# F103C8T6.net
KiCad netlist of a schematic drawn in Altium Designer
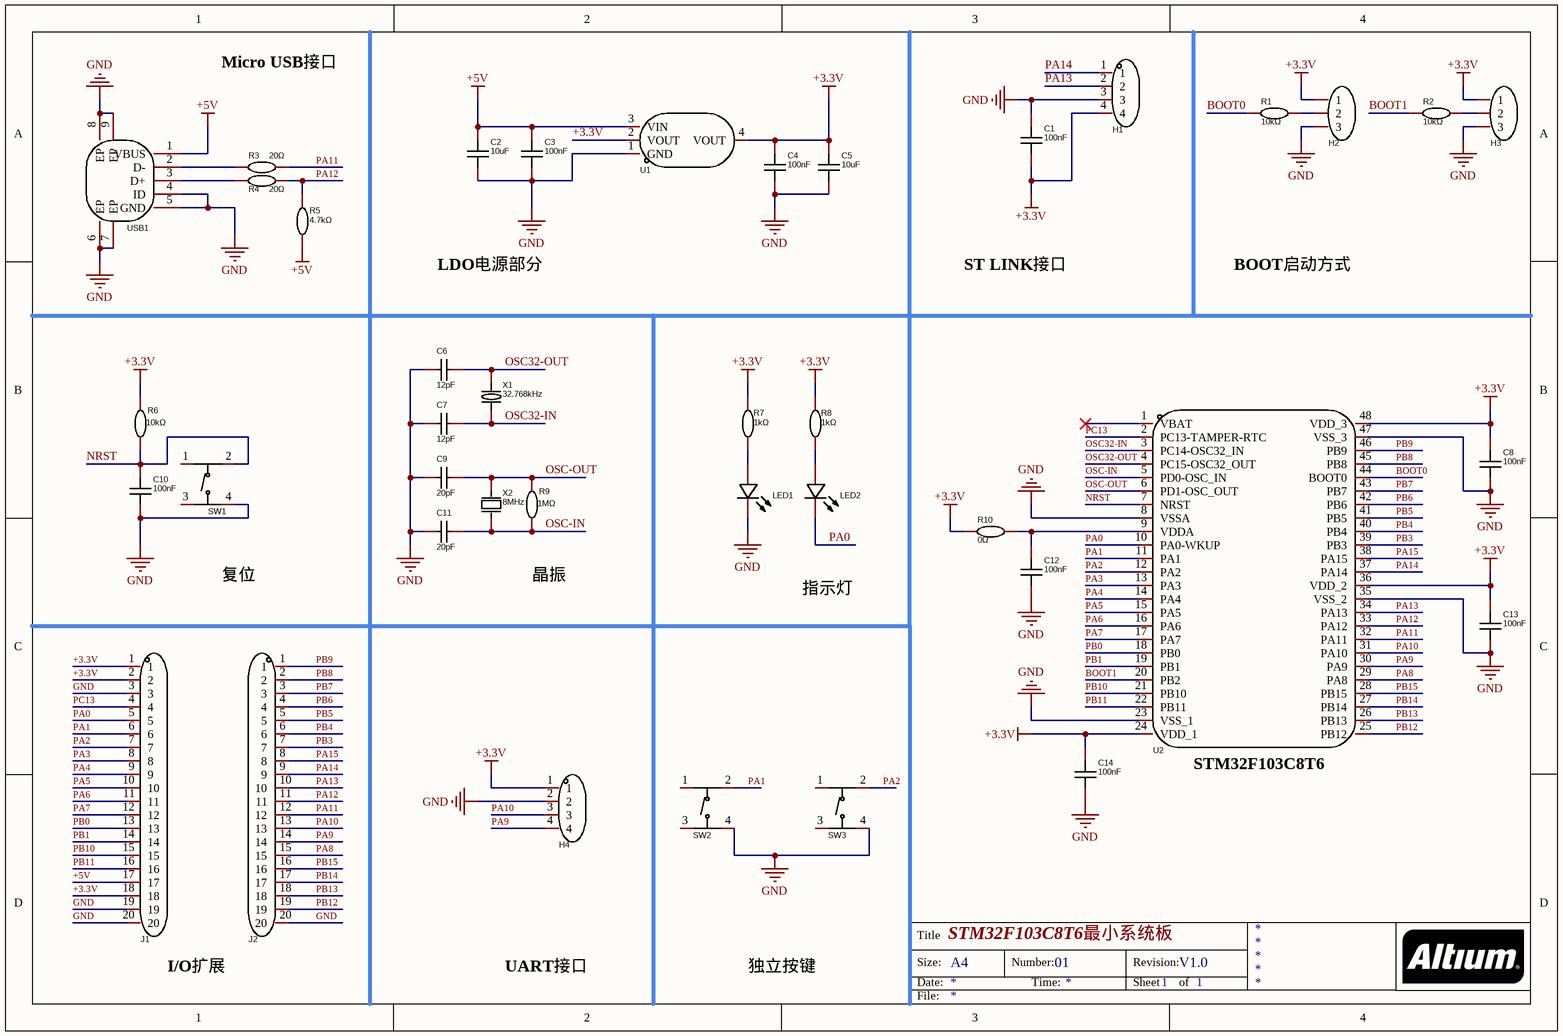
[diagram p0: F103C8T6.SchDoc]

(export (version "E")
  (design (tool "Eeschema 10.0.6"))
  (components
    (comp (ref "C1")
      (value "100nF")
      (footprint "C0603")
      (fields
        (field (name "MANUFACTURER") "YAGEO(国巨)")
        (field (name "MANUFACTURER PART") "CC0603KRX7R9BB104")
        (field (name "TOLERANCE") "±10%")
      )
      (libsource (lib "F103C8T6") (part "CAP_100nf"))
    )
    (comp (ref "C2")
      (value "10uF")
      (footprint "C0603")
      (fields
        (field (name "MANUFACTURER") "SAMSUNG(三星)")
        (field (name "MANUFACTURER PART") "CL10A106MA8NRNC")
        (field (name "TOLERANCE") "±20%")
      )
      (libsource (lib "F103C8T6") (part "CAP_10uf"))
    )
    (comp (ref "C3")
      (value "100nF")
      (footprint "C0603")
      (fields
        (field (name "MANUFACTURER") "YAGEO(国巨)")
        (field (name "MANUFACTURER PART") "CC0603KRX7R9BB104")
        (field (name "TOLERANCE") "±10%")
      )
      (libsource (lib "F103C8T6") (part "CAP_100nf"))
    )
    (comp (ref "C4")
      (value "100nF")
      (footprint "C0603")
      (fields
        (field (name "MANUFACTURER") "YAGEO(国巨)")
        (field (name "MANUFACTURER PART") "CC0603KRX7R9BB104")
        (field (name "TOLERANCE") "±10%")
      )
      (libsource (lib "F103C8T6") (part "CAP_100nf"))
    )
    (comp (ref "C5")
      (value "10uF")
      (footprint "C0603")
      (fields
        (field (name "MANUFACTURER") "SAMSUNG(三星)")
        (field (name "MANUFACTURER PART") "CL10A106MA8NRNC")
        (field (name "TOLERANCE") "±20%")
      )
      (libsource (lib "F103C8T6") (part "CAP_10uf"))
    )
    (comp (ref "C6")
      (value "12pF")
      (footprint "C0603")
      (fields
        (field (name "MANUFACTURER") "SAMSUNG(三星)")
        (field (name "MANUFACTURER PART") "CL10C120JB8NNNC")
        (field (name "TOLERANCE") "±5%")
      )
      (libsource (lib "F103C8T6") (part "CAP_12pf_0603"))
    )
    (comp (ref "C7")
      (value "12pF")
      (footprint "C0603")
      (fields
        (field (name "MANUFACTURER") "SAMSUNG(三星)")
        (field (name "MANUFACTURER PART") "CL10C120JB8NNNC")
        (field (name "TOLERANCE") "±5%")
      )
      (libsource (lib "F103C8T6") (part "CAP_12pf_0603"))
    )
    (comp (ref "C8")
      (value "100nF")
      (footprint "C0603")
      (fields
        (field (name "MANUFACTURER") "YAGEO(国巨)")
        (field (name "MANUFACTURER PART") "CC0603KRX7R9BB104")
        (field (name "TOLERANCE") "±10%")
      )
      (libsource (lib "F103C8T6") (part "CAP_100nf"))
    )
    (comp (ref "C9")
      (value "20pF")
      (footprint "C0603")
      (fields
        (field (name "MANUFACTURER") "SAMSUNG(三星)")
        (field (name "MANUFACTURER PART") "CL10C200JB8NNNC")
        (field (name "TOLERANCE") "±5%")
      )
      (libsource (lib "F103C8T6") (part "CAP_20pf_0603"))
    )
    (comp (ref "C10")
      (value "100nF")
      (footprint "C0603")
      (fields
        (field (name "MANUFACTURER") "YAGEO(国巨)")
        (field (name "MANUFACTURER PART") "CC0603KRX7R9BB104")
        (field (name "TOLERANCE") "±10%")
      )
      (libsource (lib "F103C8T6") (part "CAP_100nf"))
    )
    (comp (ref "C11")
      (value "20pF")
      (footprint "C0603")
      (fields
        (field (name "MANUFACTURER") "SAMSUNG(三星)")
        (field (name "MANUFACTURER PART") "CL10C200JB8NNNC")
        (field (name "TOLERANCE") "±5%")
      )
      (libsource (lib "F103C8T6") (part "CAP_20pf_0603"))
    )
    (comp (ref "C12")
      (value "100nF")
      (footprint "C0603")
      (fields
        (field (name "MANUFACTURER") "YAGEO(国巨)")
        (field (name "MANUFACTURER PART") "CC0603KRX7R9BB104")
        (field (name "TOLERANCE") "±10%")
      )
      (libsource (lib "F103C8T6") (part "CAP_100nf"))
    )
    (comp (ref "C13")
      (value "100nF")
      (footprint "C0603")
      (fields
        (field (name "MANUFACTURER") "YAGEO(国巨)")
        (field (name "MANUFACTURER PART") "CC0603KRX7R9BB104")
        (field (name "TOLERANCE") "±10%")
      )
      (libsource (lib "F103C8T6") (part "CAP_100nf"))
    )
    (comp (ref "C14")
      (value "100nF")
      (footprint "C0603")
      (fields
        (field (name "MANUFACTURER") "YAGEO(国巨)")
        (field (name "MANUFACTURER PART") "CC0603KRX7R9BB104")
        (field (name "TOLERANCE") "±10%")
      )
      (libsource (lib "F103C8T6") (part "CAP_100nf"))
    )
    (comp (ref "H1")
      (value "2.54-1*4P反弯排针")
      (footprint "HDR-TH_4P-P2.54-H-M-W10.4")
      (fields (field (name "MANUFACTURER") "BOOMELE(博穆精密)"))
      (libsource (lib "F103C8T6") (part "2.54-1*4P反弯排针"))
    )
    (comp (ref "H2")
      (value "2.54-1*3P针")
      (footprint "HDR-TH_3P-P2.54-V-M-1")
      (fields (field (name "MANUFACTURER") "BOOMELE(博穆精密)"))
      (libsource (lib "F103C8T6") (part "2.54-1*3P针"))
    )
    (comp (ref "H3")
      (value "2.54-1*3P针")
      (footprint "HDR-TH_3P-P2.54-V-M-1")
      (fields (field (name "MANUFACTURER") "BOOMELE(博穆精密)"))
      (libsource (lib "F103C8T6") (part "2.54-1*3P针"))
    )
    (comp (ref "H4")
      (value "PZ254V-11-04P")
      (footprint "HDR-TH_4P-P2.54-V-M")
      (fields (field (name "MANUFACTURER") "XFCN(兴飞)"))
      (libsource (lib "F103C8T6") (part "2.54-1*4P直针"))
    )
    (comp (ref "J1")
      (value "2.54-1*20P直针")
      (footprint "HDR-TH_20P-P2.54-V-M-1")
      (fields (field (name "MANUFACTURER") "BOOMELE(博穆精密)"))
      (libsource (lib "F103C8T6") (part "2.54-1*20P直针"))
    )
    (comp (ref "J2")
      (value "2.54-1*20P直针")
      (footprint "HDR-TH_20P-P2.54-V-M-1")
      (fields (field (name "MANUFACTURER") "BOOMELE(博穆精密)"))
      (libsource (lib "F103C8T6") (part "2.54-1*20P直针"))
    )
    (comp (ref "LED1")
      (value "NCD0805G1")
      (footprint "LED0805-Greed")
      (fields (field (name "MANUFACTURER") "国星光电"))
      (libsource (lib "F103C8T6") (part "LED_Greed_0805"))
    )
    (comp (ref "LED2")
      (value "NCD0805R1")
      (footprint "LED0805-Red")
      (fields (field (name "MANUFACTURER") "国星光电"))
      (libsource (lib "F103C8T6") (part "LED_Red_0805"))
    )
    (comp (ref "R1")
      (value "10kΩ")
      (footprint "R0603")
      (fields
        (field (name "MANUFACTURER") "UNI-ROYAL(厚声)")
        (field (name "MANUFACTURER PART") "0603WAF1002T5E")
        (field (name "TOLERANCE") "±1%")
      )
      (libsource (lib "F103C8T6") (part "RES_10k_0603"))
    )
    (comp (ref "R2")
      (value "10kΩ")
      (footprint "R0603")
      (fields
        (field (name "MANUFACTURER") "UNI-ROYAL(厚声)")
        (field (name "MANUFACTURER PART") "0603WAF1002T5E")
        (field (name "TOLERANCE") "±1%")
      )
      (libsource (lib "F103C8T6") (part "RES_10k_0603"))
    )
    (comp (ref "R3")
      (value "20Ω")
      (footprint "R0603")
      (fields
        (field (name "MANUFACTURER") "UNI-ROYAL(厚声)")
        (field (name "MANUFACTURER PART") "0603WAF200JT5E")
        (field (name "TOLERANCE") "±1%")
      )
      (libsource (lib "F103C8T6") (part "RES_20Ω_0603"))
    )
    (comp (ref "R4")
      (value "20Ω")
      (footprint "R0603")
      (fields
        (field (name "MANUFACTURER") "UNI-ROYAL(厚声)")
        (field (name "MANUFACTURER PART") "0603WAF200JT5E")
        (field (name "TOLERANCE") "±1%")
      )
      (libsource (lib "F103C8T6") (part "RES_20Ω_0603"))
    )
    (comp (ref "R5")
      (value "4.7kΩ")
      (footprint "R0603")
      (fields
        (field (name "MANUFACTURER") "UNI-ROYAL(厚声)")
        (field (name "MANUFACTURER PART") "0603WAF1001T5E")
        (field (name "TOLERANCE") "±1%")
      )
      (libsource (lib "F103C8T6") (part "RES_4.7K_0603"))
    )
    (comp (ref "R6")
      (value "10kΩ")
      (footprint "R0603")
      (fields
        (field (name "MANUFACTURER") "UNI-ROYAL(厚声)")
        (field (name "MANUFACTURER PART") "0603WAF1002T5E")
        (field (name "TOLERANCE") "±1%")
      )
      (libsource (lib "F103C8T6") (part "RES_10k_0603"))
    )
    (comp (ref "R7")
      (value "1kΩ")
      (footprint "R0603")
      (fields
        (field (name "MANUFACTURER") "UNI-ROYAL(厚声)")
        (field (name "MANUFACTURER PART") "0603WAF1001T5E")
        (field (name "TOLERANCE") "±1%")
      )
      (libsource (lib "F103C8T6") (part "RES_1K_0603"))
    )
    (comp (ref "R8")
      (value "1kΩ")
      (footprint "R0603")
      (fields
        (field (name "MANUFACTURER") "UNI-ROYAL(厚声)")
        (field (name "MANUFACTURER PART") "0603WAF1001T5E")
        (field (name "TOLERANCE") "±1%")
      )
      (libsource (lib "F103C8T6") (part "RES_1K_0603"))
    )
    (comp (ref "R9")
      (value "1MΩ")
      (footprint "R0603")
      (fields
        (field (name "MANUFACTURER") "UNI-ROYAL(厚声)")
        (field (name "MANUFACTURER PART") "0603WAF1002T5E")
        (field (name "TOLERANCE") "±1%")
      )
      (libsource (lib "F103C8T6") (part "RES_1M_0603"))
    )
    (comp (ref "R10")
      (value "0Ω")
      (footprint "R0603")
      (fields
        (field (name "MANUFACTURER") "UNI-ROYAL(厚声)")
        (field (name "MANUFACTURER PART") "0603WAF0000T5E")
        (field (name "TOLERANCE") "±1%")
      )
      (libsource (lib "F103C8T6") (part "RES_0Ω_0603"))
    )
    (comp (ref "SW1")
      (value "TS-1187A-B-A-B")
      (footprint "SW-SMD_4P-L5.1-W5.1-P3.70-LS6.5-TL-2")
      (fields (field (name "MANUFACTURER") "XKB Connectivity(中国星坤)"))
      (libsource (lib "F103C8T6") (part "SW"))
    )
    (comp (ref "SW2")
      (value "TS-1187A-B-A-B")
      (footprint "SW-SMD_4P-L5.1-W5.1-P3.70-LS6.5-TL-2")
      (fields (field (name "MANUFACTURER") "XKB Connectivity(中国星坤)"))
      (libsource (lib "F103C8T6") (part "SW"))
    )
    (comp (ref "SW3")
      (value "TS-1187A-B-A-B")
      (footprint "SW-SMD_4P-L5.1-W5.1-P3.70-LS6.5-TL-2")
      (fields (field (name "MANUFACTURER") "XKB Connectivity(中国星坤)"))
      (libsource (lib "F103C8T6") (part "SW"))
    )
    (comp (ref "U1")
      (value "AMS1117-3.3_C6186")
      (footprint "SOT-223-3_L6.5-W3.4-P2.30-LS7.0-BR")
      (fields (field (name "MANUFACTURER") "AMS") (field (name "MANUFACTURER PART") "AMS1117-3.3"))
      (libsource (lib "F103C8T6") (part "AMS1117-3.3_C6186"))
    )
    (comp (ref "U2")
      (value "STM32F103C8T6")
      (footprint "LQFP-48_L7.0-W7.0-P0.50-LS9.0-BL")
      (fields (field (name "MANUFACTURER") "ST(意法半导体)"))
      (libsource (lib "F103C8T6") (part "STM32F103C8T6"))
    )
    (comp (ref "USB1")
      (value "920-F52A2021S10101")
      (footprint "MICRO-USB-SMD_5P_C40957")
      (fields (field (name "MANUFACTURER") "精拓金"))
      (libsource (lib "F103C8T6") (part "Micro-B"))
    )
    (comp (ref "X1")
      (value "32.768kHz")
      (footprint "FC-135R_L3.2-W1.5")
      (fields (field (name "MANUFACTURER") "EPSON(爱普生)") (field (name "MANUFACTURER PART") "Q13FC1350000400"))
      (libsource (lib "F103C8T6") (part "32.768KHZ"))
    )
    (comp (ref "X2")
      (value "8MHz")
      (footprint "CRYSTAL-SMD_L5.0-W3.2")
      (fields (field (name "MANUFACTURER") "YXC(扬兴晶振)") (field (name "MANUFACTURER PART") "X50328MSB2GI"))
      (libsource (lib "F103C8T6") (part "8MHZ"))
    )
  )
  (nets
    (net (code "1") (name "+3.3V") (class "Default")
      (node (ref "C1") (pin "2") (pinfunction "2_2") (pintype "passive"))
      (node (ref "C13") (pin "2") (pinfunction "2_2") (pintype "passive"))
      (node (ref "C14") (pin "2") (pinfunction "2_2") (pintype "passive"))
      (node (ref "C4") (pin "2") (pinfunction "2_2") (pintype "passive"))
      (node (ref "C5") (pin "2") (pinfunction "2_2") (pintype "passive"))
      (node (ref "C8") (pin "2") (pinfunction "2_2") (pintype "passive"))
      (node (ref "H1") (pin "4") (pinfunction "4_4") (pintype "passive"))
      (node (ref "H2") (pin "1") (pinfunction "1_1") (pintype "passive"))
      (node (ref "H3") (pin "1") (pinfunction "1_1") (pintype "passive"))
      (node (ref "H4") (pin "1") (pinfunction "1_1") (pintype "passive"))
      (node (ref "J1") (pin "1") (pinfunction "1_1") (pintype "passive"))
      (node (ref "J1") (pin "18") (pinfunction "18_18") (pintype "passive"))
      (node (ref "J1") (pin "2") (pinfunction "2_2") (pintype "passive"))
      (node (ref "R10") (pin "1") (pinfunction "1_1") (pintype "passive"))
      (node (ref "R6") (pin "2") (pinfunction "2_2") (pintype "passive"))
      (node (ref "R7") (pin "2") (pinfunction "2_2") (pintype "passive"))
      (node (ref "R8") (pin "2") (pinfunction "2_2") (pintype "passive"))
      (node (ref "U1") (pin "2") (pinfunction "VOUT_2") (pintype "passive"))
      (node (ref "U1") (pin "4") (pinfunction "VOUT_4") (pintype "passive"))
      (node (ref "U2") (pin "24") (pinfunction "VDD_1_24") (pintype "passive"))
      (node (ref "U2") (pin "36") (pinfunction "VDD_2_36") (pintype "passive"))
      (node (ref "U2") (pin "48") (pinfunction "VDD_3_48") (pintype "passive"))
    )
    (net (code "2") (name "+5V") (class "Default")
      (node (ref "C2") (pin "2") (pinfunction "2_2") (pintype "passive"))
      (node (ref "C3") (pin "2") (pinfunction "2_2") (pintype "passive"))
      (node (ref "J1") (pin "17") (pinfunction "17_17") (pintype "passive"))
      (node (ref "R5") (pin "1") (pinfunction "1_1") (pintype "passive"))
      (node (ref "U1") (pin "3") (pinfunction "VIN_3") (pintype "passive"))
      (node (ref "USB1") (pin "1") (pinfunction "VBUS_1") (pintype "passive"))
    )
    (net (code "3") (name "/BOOT0") (class "Default")
      (node (ref "R1") (pin "2") (pinfunction "2_2") (pintype "passive"))
      (node (ref "U2") (pin "44") (pinfunction "BOOT0_44") (pintype "passive"))
    )
    (net (code "4") (name "/BOOT1") (class "Default")
      (node (ref "R2") (pin "2") (pinfunction "2_2") (pintype "passive"))
      (node (ref "U2") (pin "20") (pinfunction "PB2_20") (pintype "passive"))
    )
    (net (code "5") (name "/NRST") (class "Default")
      (node (ref "C10") (pin "2") (pinfunction "2_2") (pintype "passive"))
      (node (ref "R6") (pin "1") (pinfunction "1_1") (pintype "passive"))
      (node (ref "SW1") (pin "2") (pinfunction "B_2") (pintype "passive"))
      (node (ref "U2") (pin "7") (pinfunction "NRST_7") (pintype "passive"))
    )
    (net (code "6") (name "/OSC-IN") (class "Default")
      (node (ref "C11") (pin "2") (pinfunction "2_2") (pintype "passive"))
      (node (ref "R9") (pin "1") (pinfunction "1_1") (pintype "passive"))
      (node (ref "U2") (pin "5") (pinfunction "PD0-OSC_IN_5") (pintype "passive"))
      (node (ref "X2") (pin "1") (pinfunction "OSC1_1") (pintype "passive"))
    )
    (net (code "7") (name "/OSC-OUT") (class "Default")
      (node (ref "C9") (pin "2") (pinfunction "2_2") (pintype "passive"))
      (node (ref "R9") (pin "2") (pinfunction "2_2") (pintype "passive"))
      (node (ref "U2") (pin "6") (pinfunction "PD1-OSC_OUT_6") (pintype "passive"))
      (node (ref "X2") (pin "2") (pinfunction "OSC2_2") (pintype "passive"))
    )
    (net (code "8") (name "/OSC32-IN") (class "Default")
      (node (ref "C7") (pin "2") (pinfunction "2_2") (pintype "passive"))
      (node (ref "U2") (pin "3") (pinfunction "PC14-OSC32_IN_3") (pintype "passive"))
      (node (ref "X1") (pin "1") (pinfunction "1_1") (pintype "passive"))
    )
    (net (code "9") (name "/OSC32-OUT") (class "Default")
      (node (ref "C6") (pin "2") (pinfunction "2_2") (pintype "passive"))
      (node (ref "U2") (pin "4") (pinfunction "PC15-OSC32_OUT_4") (pintype "passive"))
      (node (ref "X1") (pin "2") (pinfunction "2_2") (pintype "passive"))
    )
    (net (code "10") (name "/PA0") (class "Default")
      (node (ref "J1") (pin "5") (pinfunction "5_5") (pintype "passive"))
      (node (ref "LED2") (pin "1") (pinfunction "-_1") (pintype "passive"))
      (node (ref "U2") (pin "10") (pinfunction "PA0-WKUP_10") (pintype "passive"))
    )
    (net (code "11") (name "/PA1") (class "Default")
      (node (ref "J1") (pin "6") (pinfunction "6_6") (pintype "passive"))
      (node (ref "SW2") (pin "2") (pinfunction "B_2") (pintype "passive"))
      (node (ref "U2") (pin "11") (pinfunction "PA1_11") (pintype "passive"))
    )
    (net (code "12") (name "/PA2") (class "Default")
      (node (ref "J1") (pin "7") (pinfunction "7_7") (pintype "passive"))
      (node (ref "SW3") (pin "2") (pinfunction "B_2") (pintype "passive"))
      (node (ref "U2") (pin "12") (pinfunction "PA2_12") (pintype "passive"))
    )
    (net (code "13") (name "/PA3") (class "Default")
      (node (ref "J1") (pin "8") (pinfunction "8_8") (pintype "passive"))
      (node (ref "U2") (pin "13") (pinfunction "PA3_13") (pintype "passive"))
    )
    (net (code "14") (name "/PA4") (class "Default")
      (node (ref "J1") (pin "9") (pinfunction "9_9") (pintype "passive"))
      (node (ref "U2") (pin "14") (pinfunction "PA4_14") (pintype "passive"))
    )
    (net (code "15") (name "/PA5") (class "Default")
      (node (ref "J1") (pin "10") (pinfunction "10_10") (pintype "passive"))
      (node (ref "U2") (pin "15") (pinfunction "PA5_15") (pintype "passive"))
    )
    (net (code "16") (name "/PA6") (class "Default")
      (node (ref "J1") (pin "11") (pinfunction "11_11") (pintype "passive"))
      (node (ref "U2") (pin "16") (pinfunction "PA6_16") (pintype "passive"))
    )
    (net (code "17") (name "/PA7") (class "Default")
      (node (ref "J1") (pin "12") (pinfunction "12_12") (pintype "passive"))
      (node (ref "U2") (pin "17") (pinfunction "PA7_17") (pintype "passive"))
    )
    (net (code "18") (name "/PA8") (class "Default")
      (node (ref "J2") (pin "15") (pinfunction "15_15") (pintype "passive"))
      (node (ref "U2") (pin "29") (pinfunction "PA8_29") (pintype "passive"))
    )
    (net (code "19") (name "/PA9") (class "Default")
      (node (ref "H4") (pin "4") (pinfunction "4_4") (pintype "passive"))
      (node (ref "J2") (pin "14") (pinfunction "14_14") (pintype "passive"))
      (node (ref "U2") (pin "30") (pinfunction "PA9_30") (pintype "passive"))
    )
    (net (code "20") (name "/PA10") (class "Default")
      (node (ref "H4") (pin "3") (pinfunction "3_3") (pintype "passive"))
      (node (ref "J2") (pin "13") (pinfunction "13_13") (pintype "passive"))
      (node (ref "U2") (pin "31") (pinfunction "PA10_31") (pintype "passive"))
    )
    (net (code "21") (name "/PA11") (class "Default")
      (node (ref "J2") (pin "12") (pinfunction "12_12") (pintype "passive"))
      (node (ref "R3") (pin "2") (pinfunction "2_2") (pintype "passive"))
      (node (ref "U2") (pin "32") (pinfunction "PA11_32") (pintype "passive"))
    )
    (net (code "22") (name "/PA12") (class "Default")
      (node (ref "J2") (pin "11") (pinfunction "11_11") (pintype "passive"))
      (node (ref "R4") (pin "2") (pinfunction "2_2") (pintype "passive"))
      (node (ref "R5") (pin "2") (pinfunction "2_2") (pintype "passive"))
      (node (ref "U2") (pin "33") (pinfunction "PA12_33") (pintype "passive"))
    )
    (net (code "23") (name "/PA13") (class "Default")
      (node (ref "H1") (pin "2") (pinfunction "2_2") (pintype "passive"))
      (node (ref "J2") (pin "10") (pinfunction "10_10") (pintype "passive"))
      (node (ref "U2") (pin "34") (pinfunction "PA13_34") (pintype "passive"))
    )
    (net (code "24") (name "/PA14") (class "Default")
      (node (ref "H1") (pin "1") (pinfunction "1_1") (pintype "passive"))
      (node (ref "J2") (pin "9") (pinfunction "9_9") (pintype "passive"))
      (node (ref "U2") (pin "37") (pinfunction "PA14_37") (pintype "passive"))
    )
    (net (code "25") (name "/PA15") (class "Default")
      (node (ref "J2") (pin "8") (pinfunction "8_8") (pintype "passive"))
      (node (ref "U2") (pin "38") (pinfunction "PA15_38") (pintype "passive"))
    )
    (net (code "26") (name "/PB0") (class "Default")
      (node (ref "J1") (pin "13") (pinfunction "13_13") (pintype "passive"))
      (node (ref "U2") (pin "18") (pinfunction "PB0_18") (pintype "passive"))
    )
    (net (code "27") (name "/PB1") (class "Default")
      (node (ref "J1") (pin "14") (pinfunction "14_14") (pintype "passive"))
      (node (ref "U2") (pin "19") (pinfunction "PB1_19") (pintype "passive"))
    )
    (net (code "28") (name "/PB3") (class "Default")
      (node (ref "J2") (pin "7") (pinfunction "7_7") (pintype "passive"))
      (node (ref "U2") (pin "39") (pinfunction "PB3_39") (pintype "passive"))
    )
    (net (code "29") (name "/PB4") (class "Default")
      (node (ref "J2") (pin "6") (pinfunction "6_6") (pintype "passive"))
      (node (ref "U2") (pin "40") (pinfunction "PB4_40") (pintype "passive"))
    )
    (net (code "30") (name "/PB5") (class "Default")
      (node (ref "J2") (pin "5") (pinfunction "5_5") (pintype "passive"))
      (node (ref "U2") (pin "41") (pinfunction "PB5_41") (pintype "passive"))
    )
    (net (code "31") (name "/PB6") (class "Default")
      (node (ref "J2") (pin "4") (pinfunction "4_4") (pintype "passive"))
      (node (ref "U2") (pin "42") (pinfunction "PB6_42") (pintype "passive"))
    )
    (net (code "32") (name "/PB7") (class "Default")
      (node (ref "J2") (pin "3") (pinfunction "3_3") (pintype "passive"))
      (node (ref "U2") (pin "43") (pinfunction "PB7_43") (pintype "passive"))
    )
    (net (code "33") (name "/PB8") (class "Default")
      (node (ref "J2") (pin "2") (pinfunction "2_2") (pintype "passive"))
      (node (ref "U2") (pin "45") (pinfunction "PB8_45") (pintype "passive"))
    )
    (net (code "34") (name "/PB9") (class "Default")
      (node (ref "J2") (pin "1") (pinfunction "1_1") (pintype "passive"))
      (node (ref "U2") (pin "46") (pinfunction "PB9_46") (pintype "passive"))
    )
    (net (code "35") (name "/PB10") (class "Default")
      (node (ref "J1") (pin "15") (pinfunction "15_15") (pintype "passive"))
      (node (ref "U2") (pin "21") (pinfunction "PB10_21") (pintype "passive"))
    )
    (net (code "36") (name "/PB11") (class "Default")
      (node (ref "J1") (pin "16") (pinfunction "16_16") (pintype "passive"))
      (node (ref "U2") (pin "22") (pinfunction "PB11_22") (pintype "passive"))
    )
    (net (code "37") (name "/PB12") (class "Default")
      (node (ref "J2") (pin "19") (pinfunction "19_19") (pintype "passive"))
      (node (ref "U2") (pin "25") (pinfunction "PB12_25") (pintype "passive"))
    )
    (net (code "38") (name "/PB13") (class "Default")
      (node (ref "J2") (pin "18") (pinfunction "18_18") (pintype "passive"))
      (node (ref "U2") (pin "26") (pinfunction "PB13_26") (pintype "passive"))
    )
    (net (code "39") (name "/PB14") (class "Default")
      (node (ref "J2") (pin "17") (pinfunction "17_17") (pintype "passive"))
      (node (ref "U2") (pin "27") (pinfunction "PB14_27") (pintype "passive"))
    )
    (net (code "40") (name "/PB15") (class "Default")
      (node (ref "J2") (pin "16") (pinfunction "16_16") (pintype "passive"))
      (node (ref "U2") (pin "28") (pinfunction "PB15_28") (pintype "passive"))
    )
    (net (code "41") (name "/PC13") (class "Default")
      (node (ref "J1") (pin "4") (pinfunction "4_4") (pintype "passive"))
      (node (ref "U2") (pin "2") (pinfunction "PC13-TAMPER-RTC_2") (pintype "passive"))
    )
    (net (code "42") (name "GND") (class "Default")
      (node (ref "C1") (pin "1") (pinfunction "1_1") (pintype "passive"))
      (node (ref "C10") (pin "1") (pinfunction "1_1") (pintype "passive"))
      (node (ref "C11") (pin "1") (pinfunction "1_1") (pintype "passive"))
      (node (ref "C12") (pin "1") (pinfunction "1_1") (pintype "passive"))
      (node (ref "C13") (pin "1") (pinfunction "1_1") (pintype "passive"))
      (node (ref "C14") (pin "1") (pinfunction "1_1") (pintype "passive"))
      (node (ref "C2") (pin "1") (pinfunction "1_1") (pintype "passive"))
      (node (ref "C3") (pin "1") (pinfunction "1_1") (pintype "passive"))
      (node (ref "C4") (pin "1") (pinfunction "1_1") (pintype "passive"))
      (node (ref "C5") (pin "1") (pinfunction "1_1") (pintype "passive"))
      (node (ref "C6") (pin "1") (pinfunction "1_1") (pintype "passive"))
      (node (ref "C7") (pin "1") (pinfunction "1_1") (pintype "passive"))
      (node (ref "C8") (pin "1") (pinfunction "1_1") (pintype "passive"))
      (node (ref "C9") (pin "1") (pinfunction "1_1") (pintype "passive"))
      (node (ref "H1") (pin "3") (pinfunction "3_3") (pintype "passive"))
      (node (ref "H2") (pin "3") (pinfunction "3_3") (pintype "passive"))
      (node (ref "H3") (pin "3") (pinfunction "3_3") (pintype "passive"))
      (node (ref "H4") (pin "2") (pinfunction "2_2") (pintype "passive"))
      (node (ref "J1") (pin "19") (pinfunction "19_19") (pintype "passive"))
      (node (ref "J1") (pin "20") (pinfunction "20_20") (pintype "passive"))
      (node (ref "J1") (pin "3") (pinfunction "3_3") (pintype "passive"))
      (node (ref "J2") (pin "20") (pinfunction "20_20") (pintype "passive"))
      (node (ref "LED1") (pin "2") (pinfunction "K_2") (pintype "passive"))
      (node (ref "SW1") (pin "4") (pinfunction "D_4") (pintype "passive"))
      (node (ref "SW2") (pin "4") (pinfunction "D_4") (pintype "passive"))
      (node (ref "SW3") (pin "4") (pinfunction "D_4") (pintype "passive"))
      (node (ref "U1") (pin "1") (pinfunction "GND_1") (pintype "passive"))
      (node (ref "U2") (pin "23") (pinfunction "VSS_1_23") (pintype "passive"))
      (node (ref "U2") (pin "35") (pinfunction "VSS_2_35") (pintype "passive"))
      (node (ref "U2") (pin "47") (pinfunction "VSS_3_47") (pintype "passive"))
      (node (ref "U2") (pin "8") (pinfunction "VSSA_8") (pintype "passive"))
      (node (ref "USB1") (pin "4") (pinfunction "ID_4") (pintype "passive"))
      (node (ref "USB1") (pin "5") (pinfunction "GND_5") (pintype "passive"))
      (node (ref "USB1") (pin "6") (pinfunction "EP_6") (pintype "passive"))
      (node (ref "USB1") (pin "7") (pinfunction "EP_7") (pintype "passive"))
      (node (ref "USB1") (pin "8") (pinfunction "EP_8") (pintype "passive"))
      (node (ref "USB1") (pin "9") (pinfunction "EP_9") (pintype "passive"))
    )
    (net (code "43") (name "Net-(H2-Pad2)") (class "Default")
      (node (ref "H2") (pin "2") (pinfunction "2_2") (pintype "passive"))
      (node (ref "R1") (pin "1") (pinfunction "1_1") (pintype "passive"))
    )
    (net (code "44") (name "Net-(H3-Pad2)") (class "Default")
      (node (ref "H3") (pin "2") (pinfunction "2_2") (pintype "passive"))
      (node (ref "R2") (pin "1") (pinfunction "1_1") (pintype "passive"))
    )
    (net (code "45") (name "Net-(LED1-A)") (class "Default")
      (node (ref "LED1") (pin "1") (pinfunction "A_1") (pintype "passive"))
      (node (ref "R7") (pin "1") (pinfunction "1_1") (pintype "passive"))
    )
    (net (code "46") (name "Net-(LED2-+)") (class "Default")
      (node (ref "LED2") (pin "2") (pinfunction "+_2") (pintype "passive"))
      (node (ref "R8") (pin "1") (pinfunction "1_1") (pintype "passive"))
    )
    (net (code "47") (name "Net-(U2-VDDA)") (class "Default")
      (node (ref "C12") (pin "2") (pinfunction "2_2") (pintype "passive"))
      (node (ref "R10") (pin "2") (pinfunction "2_2") (pintype "passive"))
      (node (ref "U2") (pin "9") (pinfunction "VDDA_9") (pintype "passive"))
    )
    (net (code "48") (name "Net-(USB1-D+)") (class "Default")
      (node (ref "R4") (pin "1") (pinfunction "1_1") (pintype "passive"))
      (node (ref "USB1") (pin "3") (pinfunction "D+_3") (pintype "passive"))
    )
    (net (code "49") (name "Net-(USB1-D-)") (class "Default")
      (node (ref "R3") (pin "1") (pinfunction "1_1") (pintype "passive"))
      (node (ref "USB1") (pin "2") (pinfunction "D-_2") (pintype "passive"))
    )
    (net (code "50") (name "unconnected-(SW1-A-Pad1)") (class "Default")
      (node (ref "SW1") (pin "1") (pinfunction "A_1") (pintype "passive"))
    )
    (net (code "51") (name "unconnected-(SW1-C-Pad3)") (class "Default")
      (node (ref "SW1") (pin "3") (pinfunction "C_3") (pintype "passive"))
    )
    (net (code "52") (name "unconnected-(SW2-A-Pad1)") (class "Default")
      (node (ref "SW2") (pin "1") (pinfunction "A_1") (pintype "passive"))
    )
    (net (code "53") (name "unconnected-(SW2-C-Pad3)") (class "Default")
      (node (ref "SW2") (pin "3") (pinfunction "C_3") (pintype "passive"))
    )
    (net (code "54") (name "unconnected-(SW3-A-Pad1)") (class "Default")
      (node (ref "SW3") (pin "1") (pinfunction "A_1") (pintype "passive"))
    )
    (net (code "55") (name "unconnected-(SW3-C-Pad3)") (class "Default")
      (node (ref "SW3") (pin "3") (pinfunction "C_3") (pintype "passive"))
    )
    (net (code "56") (name "unconnected-(U2-VBAT-Pad1)") (class "Default")
      (node (ref "U2") (pin "1") (pinfunction "VBAT_1") (pintype "passive+no_connect"))
    )
  )
)
